# Skaarhoj_BI8-SE-C30.net
KiCad netlist of a schematic drawn in EAGLE
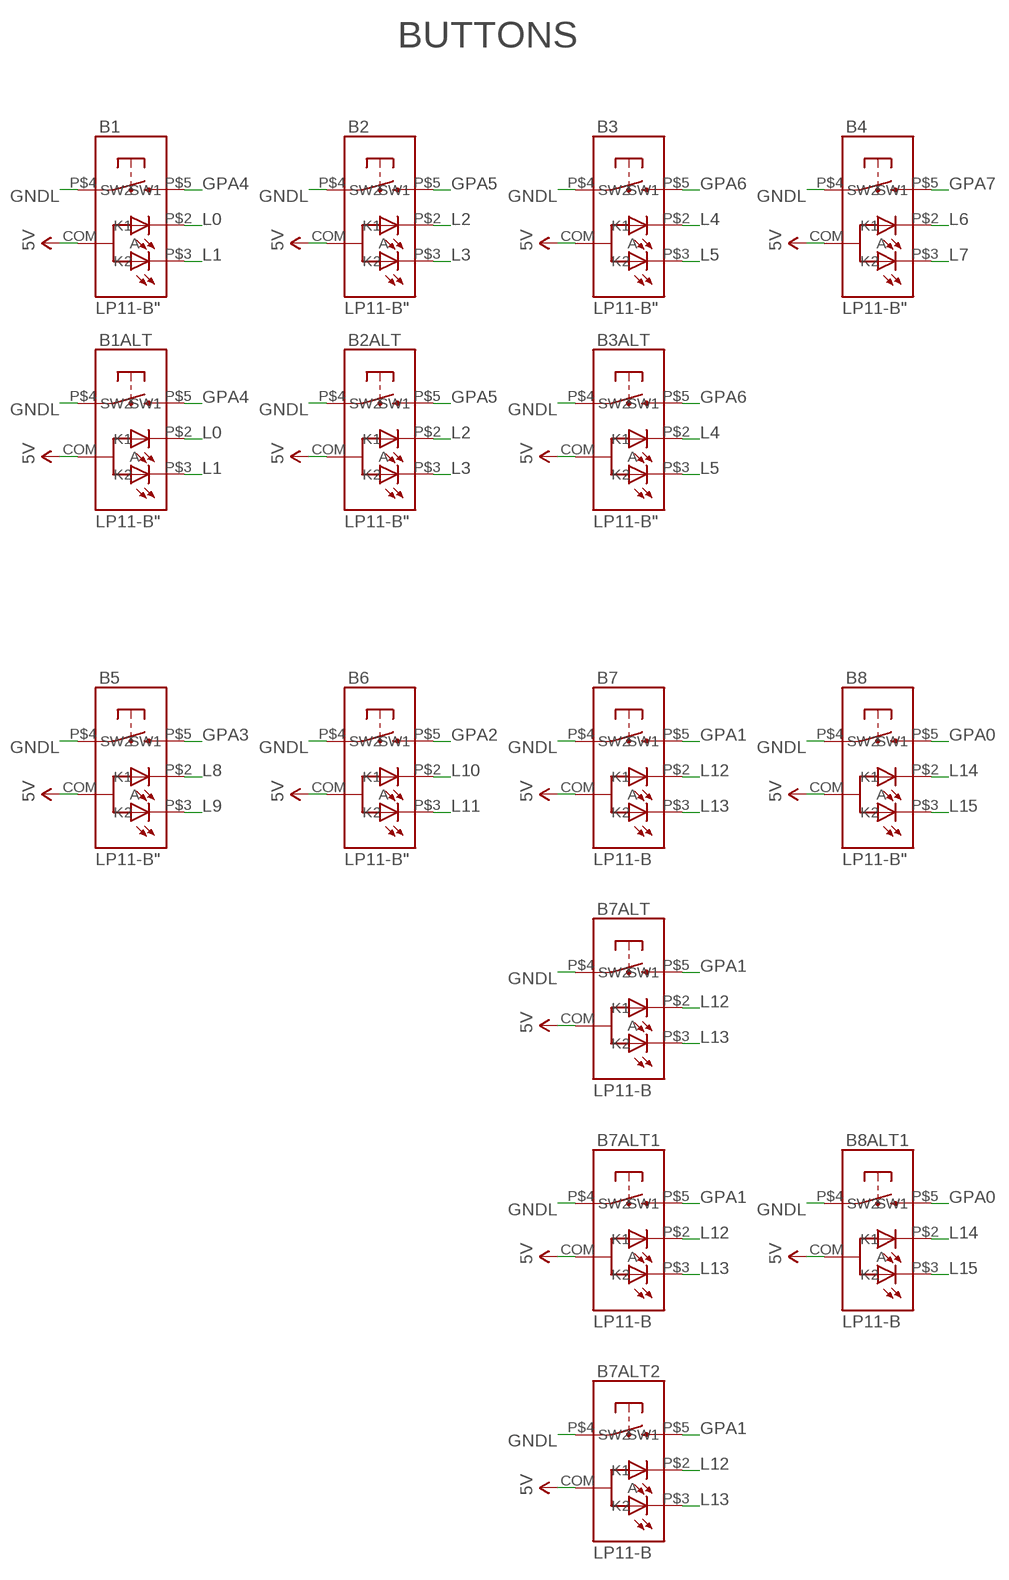
[diagram p0: schematic, sheet 1, part 1 of 2]
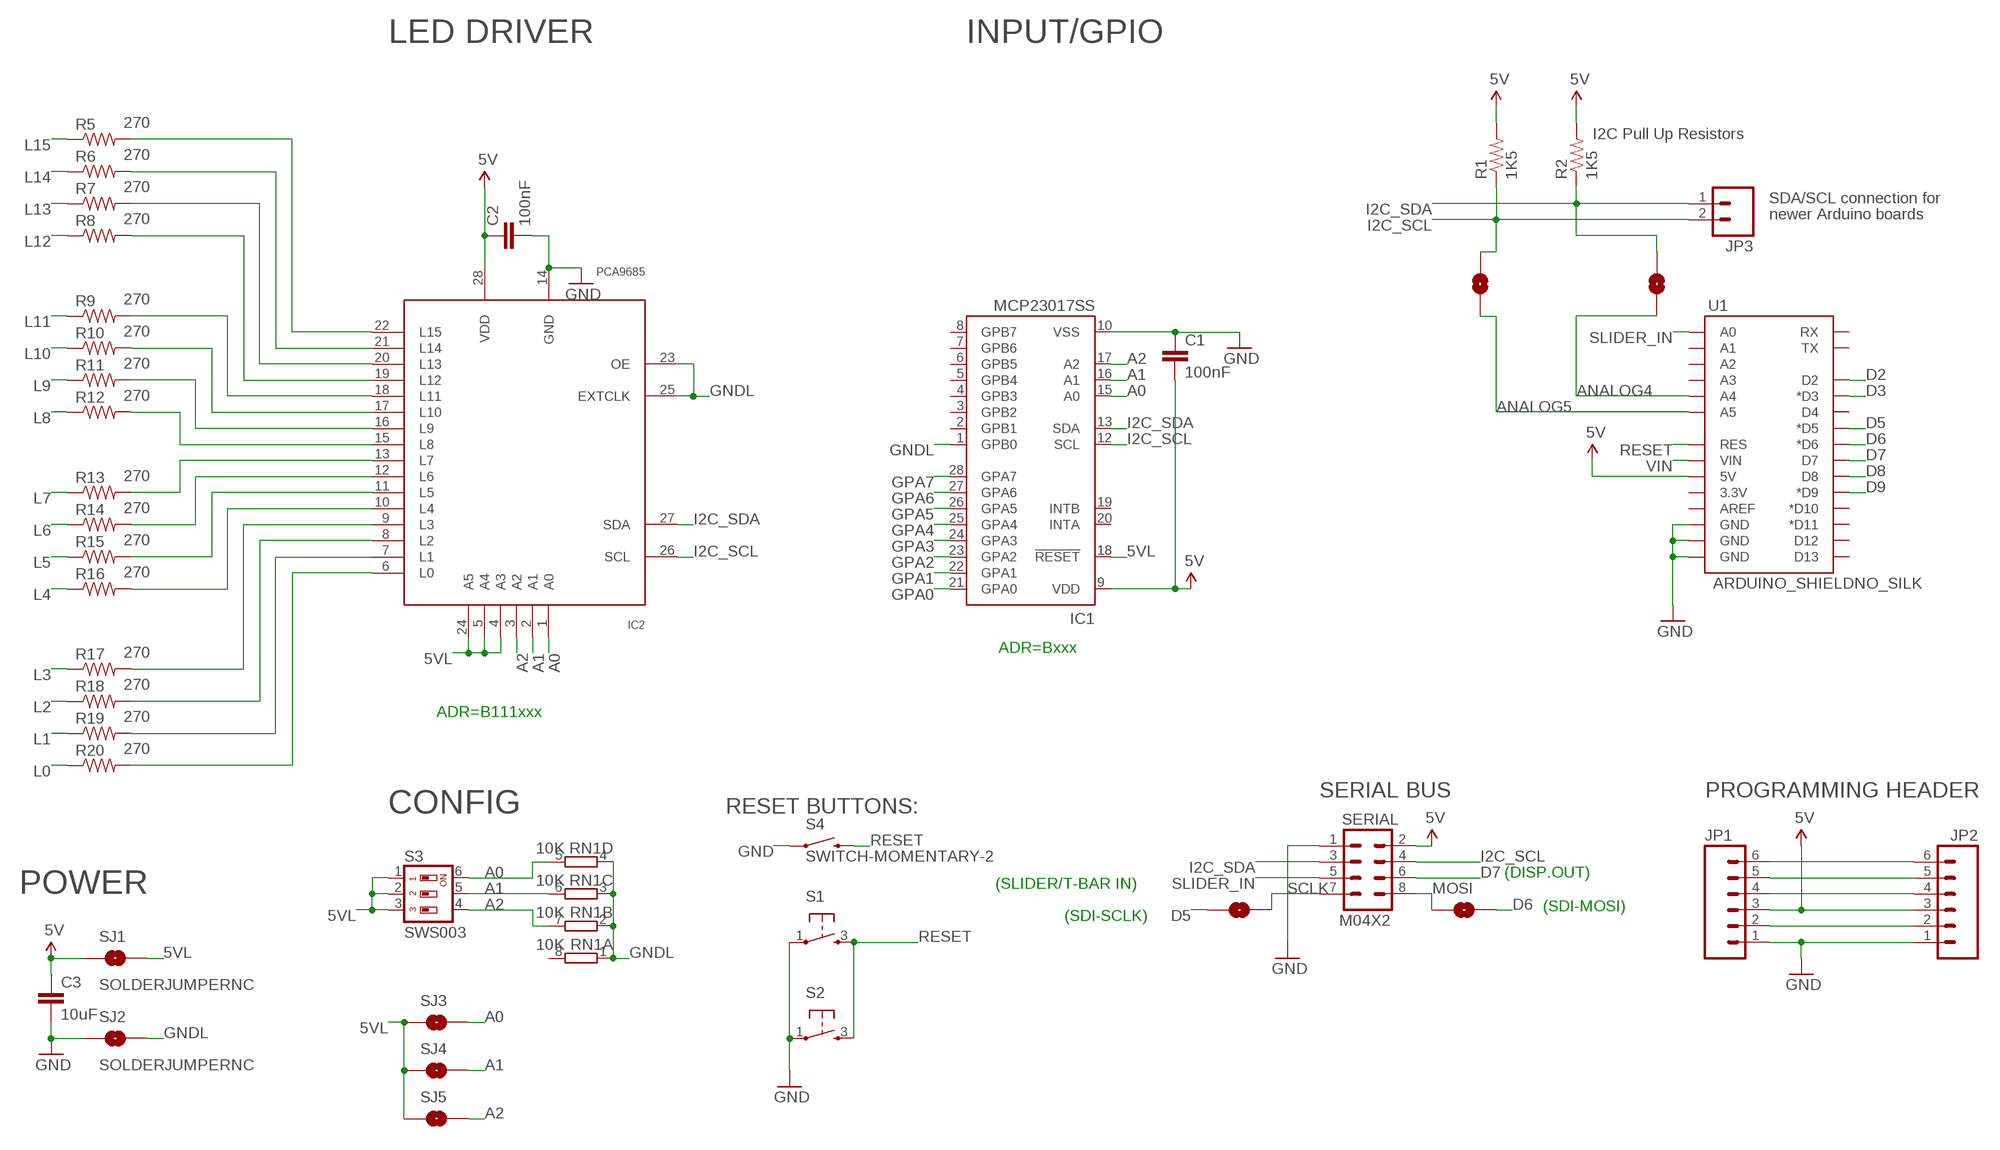
[diagram p1: schematic, sheet 1, part 2 of 2]

(export (version "E")
  (design (tool "Eeschema 10.0.6"))
  (components
    (comp (ref "B1")
      (value "LP11-B\"")
      (footprint "eagle-import:LP11")
      (libsource (lib "eagle-import") (part "LP11-B{dblquote}"))
    )
    (comp (ref "B1ALT")
      (value "LP11-B\"")
      (footprint "eagle-import:LP11")
      (libsource (lib "eagle-import") (part "LP11-B{dblquote}"))
    )
    (comp (ref "B2")
      (value "LP11-B\"")
      (footprint "eagle-import:LP11")
      (libsource (lib "eagle-import") (part "LP11-B{dblquote}"))
    )
    (comp (ref "B2ALT")
      (value "LP11-B\"")
      (footprint "eagle-import:LP11")
      (libsource (lib "eagle-import") (part "LP11-B{dblquote}"))
    )
    (comp (ref "B3")
      (value "LP11-B\"")
      (footprint "eagle-import:LP11")
      (libsource (lib "eagle-import") (part "LP11-B{dblquote}"))
    )
    (comp (ref "B3ALT")
      (value "LP11-B\"")
      (footprint "eagle-import:LP11")
      (libsource (lib "eagle-import") (part "LP11-B{dblquote}"))
    )
    (comp (ref "B4")
      (value "LP11-B\"")
      (footprint "eagle-import:LP11")
      (libsource (lib "eagle-import") (part "LP11-B{dblquote}"))
    )
    (comp (ref "B5")
      (value "LP11-B\"")
      (footprint "eagle-import:LP11")
      (libsource (lib "eagle-import") (part "LP11-B{dblquote}"))
    )
    (comp (ref "B6")
      (value "LP11-B\"")
      (footprint "eagle-import:LP11")
      (libsource (lib "eagle-import") (part "LP11-B{dblquote}"))
    )
    (comp (ref "B7")
      (value "LP11-B")
      (footprint "eagle-import:LP11_NOFIXHOLES")
      (libsource (lib "eagle-import") (part "LP11-B"))
    )
    (comp (ref "B7ALT")
      (value "LP11-B")
      (footprint "eagle-import:LP11_NOFIXHOLES")
      (libsource (lib "eagle-import") (part "LP11-B"))
    )
    (comp (ref "B7ALT1")
      (value "LP11-B")
      (footprint "eagle-import:LP11_NOFIXHOLES")
      (libsource (lib "eagle-import") (part "LP11-B"))
    )
    (comp (ref "B7ALT2")
      (value "LP11-B")
      (footprint "eagle-import:LP11_NOFIXHOLES")
      (libsource (lib "eagle-import") (part "LP11-B"))
    )
    (comp (ref "B8")
      (value "LP11-B\"")
      (footprint "eagle-import:LP11")
      (libsource (lib "eagle-import") (part "LP11-B{dblquote}"))
    )
    (comp (ref "B8ALT1")
      (value "LP11-B")
      (footprint "eagle-import:LP11_NOFIXHOLES")
      (libsource (lib "eagle-import") (part "LP11-B"))
    )
    (comp (ref "C1")
      (value "100nF")
      (footprint "eagle-import:0603-CAP")
      (libsource (lib "eagle-import") (part "CAP0603-CAP"))
    )
    (comp (ref "C2")
      (value "100nF")
      (footprint "eagle-import:0603-CAP")
      (libsource (lib "eagle-import") (part "CAP0603-CAP"))
    )
    (comp (ref "C3")
      (value "10uF")
      (footprint "eagle-import:0805")
      (libsource (lib "eagle-import") (part "CAP0805"))
    )
    (comp (ref "IC1")
      (value "MCP23017SS")
      (footprint "eagle-import:SSOP28")
      (fields
        (field (name "MF") "MICROCHIP")
        (field (name "MPN") "MCP23017-E/SS")
        (field (name "MPN_1") "MCP23017-E/SS")
        (field (name "OC_FARNELL") "1467674")
        (field (name "OC_NEWARK") "31K2960")
      )
      (libsource (lib "eagle-import") (part "MCP23017SS"))
    )
    (comp (ref "IC2")
      (value "PCA9685")
      (footprint "eagle-import:TSSOP28")
      (libsource (lib "eagle-import") (part "PCA9685"))
    )
    (comp (ref "JP1")
      (value "M06POLAR")
      (footprint "eagle-import:MOLEX-1X6")
      (libsource (lib "eagle-import") (part "M06POLAR"))
    )
    (comp (ref "JP2")
      (value "M06POLAR")
      (footprint "eagle-import:MOLEX-1X6")
      (libsource (lib "eagle-import") (part "M06POLAR"))
    )
    (comp (ref "JP3")
      (value "M02PTH")
      (footprint "eagle-import:1X02")
      (libsource (lib "eagle-import") (part "M02PTH"))
    )
    (comp (ref "MOSI->D6")
      (value "SOLDERJUMPERNC")
      (footprint "eagle-import:SJ_2S")
      (libsource (lib "eagle-import") (part "SOLDERJUMPERNC"))
    )
    (comp (ref "R1")
      (value "1K5")
      (footprint "eagle-import:0603-RES")
      (libsource (lib "eagle-import") (part "RESISTOR0603-RES"))
    )
    (comp (ref "R2")
      (value "1K5")
      (footprint "eagle-import:0603-RES")
      (libsource (lib "eagle-import") (part "RESISTOR0603-RES"))
    )
    (comp (ref "R5")
      (value "270")
      (footprint "eagle-import:0603-RES")
      (libsource (lib "eagle-import") (part "RESISTOR0603-RES"))
    )
    (comp (ref "R6")
      (value "270")
      (footprint "eagle-import:0603-RES")
      (libsource (lib "eagle-import") (part "RESISTOR0603-RES"))
    )
    (comp (ref "R7")
      (value "270")
      (footprint "eagle-import:0603-RES")
      (libsource (lib "eagle-import") (part "RESISTOR0603-RES"))
    )
    (comp (ref "R8")
      (value "270")
      (footprint "eagle-import:0603-RES")
      (libsource (lib "eagle-import") (part "RESISTOR0603-RES"))
    )
    (comp (ref "R9")
      (value "270")
      (footprint "eagle-import:0603-RES")
      (libsource (lib "eagle-import") (part "RESISTOR0603-RES"))
    )
    (comp (ref "R10")
      (value "270")
      (footprint "eagle-import:0603-RES")
      (libsource (lib "eagle-import") (part "RESISTOR0603-RES"))
    )
    (comp (ref "R11")
      (value "270")
      (footprint "eagle-import:0603-RES")
      (libsource (lib "eagle-import") (part "RESISTOR0603-RES"))
    )
    (comp (ref "R12")
      (value "270")
      (footprint "eagle-import:0603-RES")
      (libsource (lib "eagle-import") (part "RESISTOR0603-RES"))
    )
    (comp (ref "R13")
      (value "270")
      (footprint "eagle-import:0603-RES")
      (libsource (lib "eagle-import") (part "RESISTOR0603-RES"))
    )
    (comp (ref "R14")
      (value "270")
      (footprint "eagle-import:0603-RES")
      (libsource (lib "eagle-import") (part "RESISTOR0603-RES"))
    )
    (comp (ref "R15")
      (value "270")
      (footprint "eagle-import:0603-RES")
      (libsource (lib "eagle-import") (part "RESISTOR0603-RES"))
    )
    (comp (ref "R16")
      (value "270")
      (footprint "eagle-import:0603-RES")
      (libsource (lib "eagle-import") (part "RESISTOR0603-RES"))
    )
    (comp (ref "R17")
      (value "270")
      (footprint "eagle-import:0603-RES")
      (libsource (lib "eagle-import") (part "RESISTOR0603-RES"))
    )
    (comp (ref "R18")
      (value "270")
      (footprint "eagle-import:0603-RES")
      (libsource (lib "eagle-import") (part "RESISTOR0603-RES"))
    )
    (comp (ref "R19")
      (value "270")
      (footprint "eagle-import:0603-RES")
      (libsource (lib "eagle-import") (part "RESISTOR0603-RES"))
    )
    (comp (ref "R20")
      (value "270")
      (footprint "eagle-import:0603-RES")
      (libsource (lib "eagle-import") (part "RESISTOR0603-RES"))
    )
    (comp (ref "RN1")
      (value "10K")
      (footprint "eagle-import:CAY16_HAND")
      (libsource (lib "eagle-import") (part "4R-NCAY16"))
    )
    (comp (ref "S1")
      (value "TAC_SWITCH")
      (footprint "eagle-import:PUSHBUTTON")
      (libsource (lib "eagle-import") (part "TAC_SWITCH"))
    )
    (comp (ref "S2")
      (value "TAC_SWITCH")
      (footprint "eagle-import:PUSHBUTTON")
      (libsource (lib "eagle-import") (part "TAC_SWITCH"))
    )
    (comp (ref "S3")
      (value "SWS003")
      (footprint "eagle-import:SMS-003")
      (libsource (lib "eagle-import") (part "SWS003"))
    )
    (comp (ref "S3->A2")
      (value "SOLDERJUMPERNC")
      (footprint "eagle-import:SJ_2S")
      (libsource (lib "eagle-import") (part "SOLDERJUMPERNC"))
    )
    (comp (ref "S3->A3")
      (value "SOLDERJUMPERNC")
      (footprint "eagle-import:SJ_2S")
      (libsource (lib "eagle-import") (part "SOLDERJUMPERNC"))
    )
    (comp (ref "S4")
      (value "SWITCH-MOMENTARY-2")
      (footprint "eagle-import:TACTILE_SWITCH_TALL")
      (libsource (lib "eagle-import") (part "SWITCH-MOMENTARY-2"))
    )
    (comp (ref "SCLK->D5")
      (value "SOLDERJUMPERNC")
      (footprint "eagle-import:SJ_2S")
      (libsource (lib "eagle-import") (part "SOLDERJUMPERNC"))
    )
    (comp (ref "SERIAL")
      (value "M04X2")
      (footprint "eagle-import:2X4")
      (libsource (lib "eagle-import") (part "M04X2"))
    )
    (comp (ref "SJ1")
      (value "SOLDERJUMPERNC")
      (footprint "eagle-import:SJ_2S")
      (libsource (lib "eagle-import") (part "SOLDERJUMPERNC"))
    )
    (comp (ref "SJ2")
      (value "SOLDERJUMPERNC")
      (footprint "eagle-import:SJ_2S")
      (libsource (lib "eagle-import") (part "SOLDERJUMPERNC"))
    )
    (comp (ref "SJ3")
      (value "SOLDERJUMPERNC")
      (footprint "eagle-import:SJ_2S")
      (libsource (lib "eagle-import") (part "SOLDERJUMPERNC"))
    )
    (comp (ref "SJ4")
      (value "SOLDERJUMPERNC")
      (footprint "eagle-import:SJ_2S")
      (libsource (lib "eagle-import") (part "SOLDERJUMPERNC"))
    )
    (comp (ref "SJ5")
      (value "SOLDERJUMPERNC")
      (footprint "eagle-import:SJ_2S")
      (libsource (lib "eagle-import") (part "SOLDERJUMPERNC"))
    )
    (comp (ref "U1")
      (value "ARDUINO_SHIELDNO_SILK")
      (footprint "eagle-import:DUEMILANOVE_VIAS")
      (libsource (lib "eagle-import") (part "ARDUINO_SHIELDNO_SILK"))
    )
  )
  (nets
    (net (code "1") (name "/5VL") (class "Default")
      (node (ref "IC1") (pin "18") (pinfunction "~{RESET}_18") (pintype "input"))
      (node (ref "IC2") (pin "24") (pinfunction "A5_24") (pintype "input"))
      (node (ref "IC2") (pin "4") (pinfunction "A3_4") (pintype "input"))
      (node (ref "IC2") (pin "5") (pinfunction "A4_5") (pintype "input"))
      (node (ref "S3") (pin "1") (pinfunction "1_1") (pintype "passive"))
      (node (ref "S3") (pin "2") (pinfunction "2_2") (pintype "passive"))
      (node (ref "S3") (pin "3") (pinfunction "3_3") (pintype "passive"))
      (node (ref "SJ1") (pin "2") (pinfunction "2_2") (pintype "passive"))
      (node (ref "SJ3") (pin "1") (pinfunction "1_1") (pintype "passive"))
      (node (ref "SJ4") (pin "1") (pinfunction "1_1") (pintype "passive"))
      (node (ref "SJ5") (pin "1") (pinfunction "1_1") (pintype "passive"))
    )
    (net (code "2") (name "/A0") (class "Default")
      (node (ref "IC1") (pin "15") (pinfunction "A0_15") (pintype "input"))
      (node (ref "IC2") (pin "1") (pinfunction "A0_1") (pintype "input"))
      (node (ref "RN1") (pin "5") (pinfunction "2_5") (pintype "passive"))
      (node (ref "S3") (pin "6") (pinfunction "6_6") (pintype "passive"))
      (node (ref "SJ3") (pin "2") (pinfunction "2_2") (pintype "passive"))
    )
    (net (code "3") (name "/A1") (class "Default")
      (node (ref "IC1") (pin "16") (pinfunction "A1_16") (pintype "input"))
      (node (ref "IC2") (pin "2") (pinfunction "A1_2") (pintype "input"))
      (node (ref "RN1") (pin "6") (pinfunction "2_6") (pintype "passive"))
      (node (ref "S3") (pin "5") (pinfunction "5_5") (pintype "passive"))
      (node (ref "SJ4") (pin "2") (pinfunction "2_2") (pintype "passive"))
    )
    (net (code "4") (name "/A2") (class "Default")
      (node (ref "IC1") (pin "17") (pinfunction "A2_17") (pintype "input"))
      (node (ref "IC2") (pin "3") (pinfunction "A2_3") (pintype "input"))
      (node (ref "RN1") (pin "7") (pinfunction "2_7") (pintype "passive"))
      (node (ref "S3") (pin "4") (pinfunction "4_4") (pintype "passive"))
      (node (ref "SJ5") (pin "2") (pinfunction "2_2") (pintype "passive"))
    )
    (net (code "5") (name "/ANALOG4") (class "Default")
      (node (ref "S3->A3") (pin "2") (pinfunction "2_2") (pintype "passive"))
      (node (ref "U1") (pin "A4") (pinfunction "A4_A4") (pintype "bidirectional"))
    )
    (net (code "6") (name "/ANALOG5") (class "Default")
      (node (ref "S3->A2") (pin "2") (pinfunction "2_2") (pintype "passive"))
      (node (ref "U1") (pin "A5") (pinfunction "A5_A5") (pintype "bidirectional"))
    )
    (net (code "7") (name "/D2") (class "Default")
      (node (ref "U1") (pin "D2") (pinfunction "D2_D2") (pintype "bidirectional"))
    )
    (net (code "8") (name "/D3") (class "Default")
      (node (ref "U1") (pin "D3") (pinfunction "*D3_D3") (pintype "bidirectional"))
    )
    (net (code "9") (name "/D5") (class "Default")
      (node (ref "SCLK->D5") (pin "1") (pinfunction "1_1") (pintype "passive"))
      (node (ref "U1") (pin "D5") (pinfunction "*D5_D5") (pintype "bidirectional"))
    )
    (net (code "10") (name "/D6") (class "Default")
      (node (ref "MOSI->D6") (pin "2") (pinfunction "2_2") (pintype "passive"))
      (node (ref "U1") (pin "D6") (pinfunction "*D6_D6") (pintype "bidirectional"))
    )
    (net (code "11") (name "/D7") (class "Default")
      (node (ref "SERIAL") (pin "6") (pinfunction "6_6") (pintype "passive"))
      (node (ref "U1") (pin "D7") (pinfunction "D7_D7") (pintype "bidirectional"))
    )
    (net (code "12") (name "/D8") (class "Default")
      (node (ref "U1") (pin "D8") (pinfunction "D8_D8") (pintype "bidirectional"))
    )
    (net (code "13") (name "/D9") (class "Default")
      (node (ref "U1") (pin "D9") (pinfunction "*D9_D9") (pintype "bidirectional"))
    )
    (net (code "14") (name "/GNDL") (class "Default")
      (node (ref "B1") (pin "P$4") (pinfunction "SW1_P$4") (pintype "bidirectional"))
      (node (ref "B1ALT") (pin "P$4") (pinfunction "SW1_P$4") (pintype "bidirectional"))
      (node (ref "B2") (pin "P$4") (pinfunction "SW1_P$4") (pintype "bidirectional"))
      (node (ref "B2ALT") (pin "P$4") (pinfunction "SW1_P$4") (pintype "bidirectional"))
      (node (ref "B3") (pin "P$4") (pinfunction "SW1_P$4") (pintype "bidirectional"))
      (node (ref "B3ALT") (pin "P$4") (pinfunction "SW1_P$4") (pintype "bidirectional"))
      (node (ref "B4") (pin "P$4") (pinfunction "SW1_P$4") (pintype "bidirectional"))
      (node (ref "B5") (pin "P$4") (pinfunction "SW1_P$4") (pintype "bidirectional"))
      (node (ref "B6") (pin "P$4") (pinfunction "SW1_P$4") (pintype "bidirectional"))
      (node (ref "B7") (pin "P$4") (pinfunction "SW1_P$4") (pintype "bidirectional"))
      (node (ref "B7ALT") (pin "P$4") (pinfunction "SW1_P$4") (pintype "bidirectional"))
      (node (ref "B7ALT1") (pin "P$4") (pinfunction "SW1_P$4") (pintype "bidirectional"))
      (node (ref "B7ALT2") (pin "P$4") (pinfunction "SW1_P$4") (pintype "bidirectional"))
      (node (ref "B8") (pin "P$4") (pinfunction "SW1_P$4") (pintype "bidirectional"))
      (node (ref "B8ALT1") (pin "P$4") (pinfunction "SW1_P$4") (pintype "bidirectional"))
      (node (ref "IC1") (pin "1") (pinfunction "GPB0_1") (pintype "bidirectional"))
      (node (ref "IC2") (pin "23") (pinfunction "OE_23") (pintype "input"))
      (node (ref "IC2") (pin "25") (pinfunction "EXTCLK_25") (pintype "input"))
      (node (ref "RN1") (pin "1") (pinfunction "1_1") (pintype "passive"))
      (node (ref "RN1") (pin "2") (pinfunction "1_2") (pintype "passive"))
      (node (ref "RN1") (pin "3") (pinfunction "1_3") (pintype "passive"))
      (node (ref "RN1") (pin "4") (pinfunction "1_4") (pintype "passive"))
      (node (ref "SJ2") (pin "2") (pinfunction "2_2") (pintype "passive"))
    )
    (net (code "15") (name "/GPA0") (class "Default")
      (node (ref "B8") (pin "P$5") (pinfunction "SW2_P$5") (pintype "bidirectional"))
      (node (ref "B8ALT1") (pin "P$5") (pinfunction "SW2_P$5") (pintype "bidirectional"))
      (node (ref "IC1") (pin "21") (pinfunction "GPA0_21") (pintype "bidirectional"))
    )
    (net (code "16") (name "/GPA1") (class "Default")
      (node (ref "B7") (pin "P$5") (pinfunction "SW2_P$5") (pintype "bidirectional"))
      (node (ref "B7ALT") (pin "P$5") (pinfunction "SW2_P$5") (pintype "bidirectional"))
      (node (ref "B7ALT1") (pin "P$5") (pinfunction "SW2_P$5") (pintype "bidirectional"))
      (node (ref "B7ALT2") (pin "P$5") (pinfunction "SW2_P$5") (pintype "bidirectional"))
      (node (ref "IC1") (pin "22") (pinfunction "GPA1_22") (pintype "bidirectional"))
    )
    (net (code "17") (name "/GPA2") (class "Default")
      (node (ref "B6") (pin "P$5") (pinfunction "SW2_P$5") (pintype "bidirectional"))
      (node (ref "IC1") (pin "23") (pinfunction "GPA2_23") (pintype "bidirectional"))
    )
    (net (code "18") (name "/GPA3") (class "Default")
      (node (ref "B5") (pin "P$5") (pinfunction "SW2_P$5") (pintype "bidirectional"))
      (node (ref "IC1") (pin "24") (pinfunction "GPA3_24") (pintype "bidirectional"))
    )
    (net (code "19") (name "/GPA4") (class "Default")
      (node (ref "B1") (pin "P$5") (pinfunction "SW2_P$5") (pintype "bidirectional"))
      (node (ref "B1ALT") (pin "P$5") (pinfunction "SW2_P$5") (pintype "bidirectional"))
      (node (ref "IC1") (pin "25") (pinfunction "GPA4_25") (pintype "bidirectional"))
    )
    (net (code "20") (name "/GPA5") (class "Default")
      (node (ref "B2") (pin "P$5") (pinfunction "SW2_P$5") (pintype "bidirectional"))
      (node (ref "B2ALT") (pin "P$5") (pinfunction "SW2_P$5") (pintype "bidirectional"))
      (node (ref "IC1") (pin "26") (pinfunction "GPA5_26") (pintype "bidirectional"))
    )
    (net (code "21") (name "/GPA6") (class "Default")
      (node (ref "B3") (pin "P$5") (pinfunction "SW2_P$5") (pintype "bidirectional"))
      (node (ref "B3ALT") (pin "P$5") (pinfunction "SW2_P$5") (pintype "bidirectional"))
      (node (ref "IC1") (pin "27") (pinfunction "GPA6_27") (pintype "bidirectional"))
    )
    (net (code "22") (name "/GPA7") (class "Default")
      (node (ref "B4") (pin "P$5") (pinfunction "SW2_P$5") (pintype "bidirectional"))
      (node (ref "IC1") (pin "28") (pinfunction "GPA7_28") (pintype "bidirectional"))
    )
    (net (code "23") (name "/I2C_SCL") (class "Default")
      (node (ref "IC1") (pin "12") (pinfunction "SCL_12") (pintype "input"))
      (node (ref "IC2") (pin "26") (pinfunction "SCL_26") (pintype "input"))
      (node (ref "JP3") (pin "2") (pinfunction "2_2") (pintype "passive"))
      (node (ref "R1") (pin "1") (pinfunction "1_1") (pintype "passive"))
      (node (ref "S3->A2") (pin "1") (pinfunction "1_1") (pintype "passive"))
      (node (ref "SERIAL") (pin "4") (pinfunction "4_4") (pintype "passive"))
    )
    (net (code "24") (name "/I2C_SDA") (class "Default")
      (node (ref "IC1") (pin "13") (pinfunction "SDA_13") (pintype "bidirectional"))
      (node (ref "IC2") (pin "27") (pinfunction "SDA_27") (pintype "input"))
      (node (ref "JP3") (pin "1") (pinfunction "1_1") (pintype "passive"))
      (node (ref "R2") (pin "1") (pinfunction "1_1") (pintype "passive"))
      (node (ref "S3->A3") (pin "1") (pinfunction "1_1") (pintype "passive"))
      (node (ref "SERIAL") (pin "3") (pinfunction "3_3") (pintype "passive"))
    )
    (net (code "25") (name "/L0") (class "Default")
      (node (ref "B1") (pin "P$2") (pinfunction "K1_P$2") (pintype "bidirectional"))
      (node (ref "B1ALT") (pin "P$2") (pinfunction "K1_P$2") (pintype "bidirectional"))
      (node (ref "R20") (pin "1") (pinfunction "1_1") (pintype "passive"))
    )
    (net (code "26") (name "/L1") (class "Default")
      (node (ref "B1") (pin "P$3") (pinfunction "K2_P$3") (pintype "bidirectional"))
      (node (ref "B1ALT") (pin "P$3") (pinfunction "K2_P$3") (pintype "bidirectional"))
      (node (ref "R19") (pin "1") (pinfunction "1_1") (pintype "passive"))
    )
    (net (code "27") (name "/L2") (class "Default")
      (node (ref "B2") (pin "P$2") (pinfunction "K1_P$2") (pintype "bidirectional"))
      (node (ref "B2ALT") (pin "P$2") (pinfunction "K1_P$2") (pintype "bidirectional"))
      (node (ref "R18") (pin "1") (pinfunction "1_1") (pintype "passive"))
    )
    (net (code "28") (name "/L3") (class "Default")
      (node (ref "B2") (pin "P$3") (pinfunction "K2_P$3") (pintype "bidirectional"))
      (node (ref "B2ALT") (pin "P$3") (pinfunction "K2_P$3") (pintype "bidirectional"))
      (node (ref "R17") (pin "1") (pinfunction "1_1") (pintype "passive"))
    )
    (net (code "29") (name "/L4") (class "Default")
      (node (ref "B3") (pin "P$2") (pinfunction "K1_P$2") (pintype "bidirectional"))
      (node (ref "B3ALT") (pin "P$2") (pinfunction "K1_P$2") (pintype "bidirectional"))
      (node (ref "R16") (pin "1") (pinfunction "1_1") (pintype "passive"))
    )
    (net (code "30") (name "/L5") (class "Default")
      (node (ref "B3") (pin "P$3") (pinfunction "K2_P$3") (pintype "bidirectional"))
      (node (ref "B3ALT") (pin "P$3") (pinfunction "K2_P$3") (pintype "bidirectional"))
      (node (ref "R15") (pin "1") (pinfunction "1_1") (pintype "passive"))
    )
    (net (code "31") (name "/L6") (class "Default")
      (node (ref "B4") (pin "P$2") (pinfunction "K1_P$2") (pintype "bidirectional"))
      (node (ref "R14") (pin "1") (pinfunction "1_1") (pintype "passive"))
    )
    (net (code "32") (name "/L7") (class "Default")
      (node (ref "B4") (pin "P$3") (pinfunction "K2_P$3") (pintype "bidirectional"))
      (node (ref "R13") (pin "1") (pinfunction "1_1") (pintype "passive"))
    )
    (net (code "33") (name "/L8") (class "Default")
      (node (ref "B5") (pin "P$2") (pinfunction "K1_P$2") (pintype "bidirectional"))
      (node (ref "R12") (pin "1") (pinfunction "1_1") (pintype "passive"))
    )
    (net (code "34") (name "/L9") (class "Default")
      (node (ref "B5") (pin "P$3") (pinfunction "K2_P$3") (pintype "bidirectional"))
      (node (ref "R11") (pin "1") (pinfunction "1_1") (pintype "passive"))
    )
    (net (code "35") (name "/L10") (class "Default")
      (node (ref "B6") (pin "P$2") (pinfunction "K1_P$2") (pintype "bidirectional"))
      (node (ref "R10") (pin "1") (pinfunction "1_1") (pintype "passive"))
    )
    (net (code "36") (name "/L11") (class "Default")
      (node (ref "B6") (pin "P$3") (pinfunction "K2_P$3") (pintype "bidirectional"))
      (node (ref "R9") (pin "1") (pinfunction "1_1") (pintype "passive"))
    )
    (net (code "37") (name "/L12") (class "Default")
      (node (ref "B7") (pin "P$2") (pinfunction "K1_P$2") (pintype "bidirectional"))
      (node (ref "B7ALT") (pin "P$2") (pinfunction "K1_P$2") (pintype "bidirectional"))
      (node (ref "B7ALT1") (pin "P$2") (pinfunction "K1_P$2") (pintype "bidirectional"))
      (node (ref "B7ALT2") (pin "P$2") (pinfunction "K1_P$2") (pintype "bidirectional"))
      (node (ref "R8") (pin "1") (pinfunction "1_1") (pintype "passive"))
    )
    (net (code "38") (name "/L13") (class "Default")
      (node (ref "B7") (pin "P$3") (pinfunction "K2_P$3") (pintype "bidirectional"))
      (node (ref "B7ALT") (pin "P$3") (pinfunction "K2_P$3") (pintype "bidirectional"))
      (node (ref "B7ALT1") (pin "P$3") (pinfunction "K2_P$3") (pintype "bidirectional"))
      (node (ref "B7ALT2") (pin "P$3") (pinfunction "K2_P$3") (pintype "bidirectional"))
      (node (ref "R7") (pin "1") (pinfunction "1_1") (pintype "passive"))
    )
    (net (code "39") (name "/L14") (class "Default")
      (node (ref "B8") (pin "P$2") (pinfunction "K1_P$2") (pintype "bidirectional"))
      (node (ref "B8ALT1") (pin "P$2") (pinfunction "K1_P$2") (pintype "bidirectional"))
      (node (ref "R6") (pin "1") (pinfunction "1_1") (pintype "passive"))
    )
    (net (code "40") (name "/L15") (class "Default")
      (node (ref "B8") (pin "P$3") (pinfunction "K2_P$3") (pintype "bidirectional"))
      (node (ref "B8ALT1") (pin "P$3") (pinfunction "K2_P$3") (pintype "bidirectional"))
      (node (ref "R5") (pin "1") (pinfunction "1_1") (pintype "passive"))
    )
    (net (code "41") (name "/MOSI") (class "Default")
      (node (ref "MOSI->D6") (pin "1") (pinfunction "1_1") (pintype "passive"))
      (node (ref "SERIAL") (pin "8") (pinfunction "8_8") (pintype "passive"))
    )
    (net (code "42") (name "/RESET") (class "Default")
      (node (ref "S1") (pin "3") (pinfunction "3_3") (pintype "passive"))
      (node (ref "S2") (pin "3") (pinfunction "3_3") (pintype "passive"))
      (node (ref "S4") (pin "B2") (pinfunction "2_B2") (pintype "passive"))
      (node (ref "U1") (pin "RES") (pinfunction "RES_RES") (pintype "bidirectional"))
    )
    (net (code "43") (name "/SCLK") (class "Default")
      (node (ref "SCLK->D5") (pin "2") (pinfunction "2_2") (pintype "passive"))
      (node (ref "SERIAL") (pin "7") (pinfunction "7_7") (pintype "passive"))
    )
    (net (code "44") (name "/SLIDER_IN") (class "Default")
      (node (ref "SERIAL") (pin "5") (pinfunction "5_5") (pintype "passive"))
      (node (ref "U1") (pin "A0") (pinfunction "A0_A0") (pintype "bidirectional"))
    )
    (net (code "45") (name "/VIN") (class "Default")
      (node (ref "U1") (pin "VIN") (pinfunction "VIN_VIN") (pintype "bidirectional"))
    )
    (net (code "46") (name "5V") (class "Default")
      (node (ref "B1") (pin "COM") (pinfunction "A_COM") (pintype "bidirectional"))
      (node (ref "B1ALT") (pin "COM") (pinfunction "A_COM") (pintype "bidirectional"))
      (node (ref "B2") (pin "COM") (pinfunction "A_COM") (pintype "bidirectional"))
      (node (ref "B2ALT") (pin "COM") (pinfunction "A_COM") (pintype "bidirectional"))
      (node (ref "B3") (pin "COM") (pinfunction "A_COM") (pintype "bidirectional"))
      (node (ref "B3ALT") (pin "COM") (pinfunction "A_COM") (pintype "bidirectional"))
      (node (ref "B4") (pin "COM") (pinfunction "A_COM") (pintype "bidirectional"))
      (node (ref "B5") (pin "COM") (pinfunction "A_COM") (pintype "bidirectional"))
      (node (ref "B6") (pin "COM") (pinfunction "A_COM") (pintype "bidirectional"))
      (node (ref "B7") (pin "COM") (pinfunction "A_COM") (pintype "bidirectional"))
      (node (ref "B7ALT") (pin "COM") (pinfunction "A_COM") (pintype "bidirectional"))
      (node (ref "B7ALT1") (pin "COM") (pinfunction "A_COM") (pintype "bidirectional"))
      (node (ref "B7ALT2") (pin "COM") (pinfunction "A_COM") (pintype "bidirectional"))
      (node (ref "B8") (pin "COM") (pinfunction "A_COM") (pintype "bidirectional"))
      (node (ref "B8ALT1") (pin "COM") (pinfunction "A_COM") (pintype "bidirectional"))
      (node (ref "C1") (pin "2") (pinfunction "2_2") (pintype "passive"))
      (node (ref "C2") (pin "1") (pinfunction "1_1") (pintype "passive"))
      (node (ref "C3") (pin "1") (pinfunction "1_1") (pintype "passive"))
      (node (ref "IC1") (pin "9") (pinfunction "VDD_9") (pintype "power_in"))
      (node (ref "IC2") (pin "28") (pinfunction "VDD_28") (pintype "power_in"))
      (node (ref "JP1") (pin "3") (pinfunction "3_3") (pintype "passive"))
      (node (ref "JP2") (pin "3") (pinfunction "3_3") (pintype "passive"))
      (node (ref "R1") (pin "2") (pinfunction "2_2") (pintype "passive"))
      (node (ref "R2") (pin "2") (pinfunction "2_2") (pintype "passive"))
      (node (ref "SERIAL") (pin "2") (pinfunction "2_2") (pintype "passive"))
      (node (ref "SJ1") (pin "1") (pinfunction "1_1") (pintype "passive"))
      (node (ref "U1") (pin "5V") (pinfunction "5V_5V") (pintype "bidirectional"))
    )
    (net (code "47") (name "GND") (class "Default")
      (node (ref "C1") (pin "1") (pinfunction "1_1") (pintype "passive"))
      (node (ref "C2") (pin "2") (pinfunction "2_2") (pintype "passive"))
      (node (ref "C3") (pin "2") (pinfunction "2_2") (pintype "passive"))
      (node (ref "IC1") (pin "10") (pinfunction "VSS_10") (pintype "power_in"))
      (node (ref "IC2") (pin "14") (pinfunction "GND_14") (pintype "power_in"))
      (node (ref "JP1") (pin "1") (pinfunction "1_1") (pintype "passive"))
      (node (ref "JP2") (pin "1") (pinfunction "1_1") (pintype "passive"))
      (node (ref "S1") (pin "1") (pinfunction "1_1") (pintype "passive"))
      (node (ref "S2") (pin "1") (pinfunction "1_1") (pintype "passive"))
      (node (ref "S4") (pin "A2") (pinfunction "1_A2") (pintype "passive"))
      (node (ref "SERIAL") (pin "1") (pinfunction "1_1") (pintype "passive"))
      (node (ref "SJ2") (pin "1") (pinfunction "1_1") (pintype "passive"))
      (node (ref "U1") (pin "GND@0") (pinfunction "GND_GND@0") (pintype "bidirectional"))
      (node (ref "U1") (pin "GND@1") (pinfunction "GND_GND@1") (pintype "bidirectional"))
      (node (ref "U1") (pin "GND@2") (pinfunction "GND_GND@2") (pintype "bidirectional"))
    )
    (net (code "48") (name "Net-(IC2-L0)") (class "Default")
      (node (ref "IC2") (pin "6") (pinfunction "L0_6") (pintype "output"))
      (node (ref "R20") (pin "2") (pinfunction "2_2") (pintype "passive"))
    )
    (net (code "49") (name "Net-(IC2-L1)") (class "Default")
      (node (ref "IC2") (pin "7") (pinfunction "L1_7") (pintype "output"))
      (node (ref "R19") (pin "2") (pinfunction "2_2") (pintype "passive"))
    )
    (net (code "50") (name "Net-(IC2-L2)") (class "Default")
      (node (ref "IC2") (pin "8") (pinfunction "L2_8") (pintype "output"))
      (node (ref "R18") (pin "2") (pinfunction "2_2") (pintype "passive"))
    )
    (net (code "51") (name "Net-(IC2-L3)") (class "Default")
      (node (ref "IC2") (pin "9") (pinfunction "L3_9") (pintype "output"))
      (node (ref "R17") (pin "2") (pinfunction "2_2") (pintype "passive"))
    )
    (net (code "52") (name "Net-(IC2-L4)") (class "Default")
      (node (ref "IC2") (pin "10") (pinfunction "L4_10") (pintype "output"))
      (node (ref "R16") (pin "2") (pinfunction "2_2") (pintype "passive"))
    )
    (net (code "53") (name "Net-(IC2-L5)") (class "Default")
      (node (ref "IC2") (pin "11") (pinfunction "L5_11") (pintype "output"))
      (node (ref "R15") (pin "2") (pinfunction "2_2") (pintype "passive"))
    )
    (net (code "54") (name "Net-(IC2-L6)") (class "Default")
      (node (ref "IC2") (pin "12") (pinfunction "L6_12") (pintype "output"))
      (node (ref "R14") (pin "2") (pinfunction "2_2") (pintype "passive"))
    )
    (net (code "55") (name "Net-(IC2-L7)") (class "Default")
      (node (ref "IC2") (pin "13") (pinfunction "L7_13") (pintype "output"))
      (node (ref "R13") (pin "2") (pinfunction "2_2") (pintype "passive"))
    )
    (net (code "56") (name "Net-(IC2-L8)") (class "Default")
      (node (ref "IC2") (pin "15") (pinfunction "L8_15") (pintype "output"))
      (node (ref "R12") (pin "2") (pinfunction "2_2") (pintype "passive"))
    )
    (net (code "57") (name "Net-(IC2-L9)") (class "Default")
      (node (ref "IC2") (pin "16") (pinfunction "L9_16") (pintype "output"))
      (node (ref "R11") (pin "2") (pinfunction "2_2") (pintype "passive"))
    )
    (net (code "58") (name "Net-(IC2-L10)") (class "Default")
      (node (ref "IC2") (pin "17") (pinfunction "L10_17") (pintype "output"))
      (node (ref "R10") (pin "2") (pinfunction "2_2") (pintype "passive"))
    )
    (net (code "59") (name "Net-(IC2-L11)") (class "Default")
      (node (ref "IC2") (pin "18") (pinfunction "L11_18") (pintype "output"))
      (node (ref "R9") (pin "2") (pinfunction "2_2") (pintype "passive"))
    )
    (net (code "60") (name "Net-(IC2-L12)") (class "Default")
      (node (ref "IC2") (pin "19") (pinfunction "L12_19") (pintype "output"))
      (node (ref "R8") (pin "2") (pinfunction "2_2") (pintype "passive"))
    )
    (net (code "61") (name "Net-(IC2-L13)") (class "Default")
      (node (ref "IC2") (pin "20") (pinfunction "L13_20") (pintype "output"))
      (node (ref "R7") (pin "2") (pinfunction "2_2") (pintype "passive"))
    )
    (net (code "62") (name "Net-(IC2-L14)") (class "Default")
      (node (ref "IC2") (pin "21") (pinfunction "L14_21") (pintype "output"))
      (node (ref "R6") (pin "2") (pinfunction "2_2") (pintype "passive"))
    )
    (net (code "63") (name "Net-(IC2-L15)") (class "Default")
      (node (ref "IC2") (pin "22") (pinfunction "L15_22") (pintype "output"))
      (node (ref "R5") (pin "2") (pinfunction "2_2") (pintype "passive"))
    )
    (net (code "64") (name "Net-(JP1-Pad2)") (class "Default")
      (node (ref "JP1") (pin "2") (pinfunction "2_2") (pintype "passive"))
      (node (ref "JP2") (pin "2") (pinfunction "2_2") (pintype "passive"))
    )
    (net (code "65") (name "Net-(JP1-Pad4)") (class "Default")
      (node (ref "JP1") (pin "4") (pinfunction "4_4") (pintype "passive"))
      (node (ref "JP2") (pin "4") (pinfunction "4_4") (pintype "passive"))
    )
    (net (code "66") (name "Net-(JP1-Pad5)") (class "Default")
      (node (ref "JP1") (pin "5") (pinfunction "5_5") (pintype "passive"))
      (node (ref "JP2") (pin "5") (pinfunction "5_5") (pintype "passive"))
    )
    (net (code "67") (name "Net-(JP1-Pad6)") (class "Default")
      (node (ref "JP1") (pin "6") (pinfunction "6_6") (pintype "passive"))
      (node (ref "JP2") (pin "6") (pinfunction "6_6") (pintype "passive"))
    )
    (net (code "68") (name "unconnected-(IC1-GPB1-Pad2)") (class "Default")
      (node (ref "IC1") (pin "2") (pinfunction "GPB1_2") (pintype "bidirectional"))
    )
    (net (code "69") (name "unconnected-(IC1-GPB2-Pad3)") (class "Default")
      (node (ref "IC1") (pin "3") (pinfunction "GPB2_3") (pintype "bidirectional"))
    )
    (net (code "70") (name "unconnected-(IC1-GPB3-Pad4)") (class "Default")
      (node (ref "IC1") (pin "4") (pinfunction "GPB3_4") (pintype "bidirectional"))
    )
    (net (code "71") (name "unconnected-(IC1-GPB4-Pad5)") (class "Default")
      (node (ref "IC1") (pin "5") (pinfunction "GPB4_5") (pintype "bidirectional"))
    )
    (net (code "72") (name "unconnected-(IC1-GPB5-Pad6)") (class "Default")
      (node (ref "IC1") (pin "6") (pinfunction "GPB5_6") (pintype "bidirectional"))
    )
    (net (code "73") (name "unconnected-(IC1-GPB6-Pad7)") (class "Default")
      (node (ref "IC1") (pin "7") (pinfunction "GPB6_7") (pintype "bidirectional"))
    )
    (net (code "74") (name "unconnected-(IC1-GPB7-Pad8)") (class "Default")
      (node (ref "IC1") (pin "8") (pinfunction "GPB7_8") (pintype "bidirectional"))
    )
    (net (code "75") (name "unconnected-(IC1-INTA-Pad20)") (class "Default")
      (node (ref "IC1") (pin "20") (pinfunction "INTA_20") (pintype "output"))
    )
    (net (code "76") (name "unconnected-(IC1-INTB-Pad19)") (class "Default")
      (node (ref "IC1") (pin "19") (pinfunction "INTB_19") (pintype "output"))
    )
    (net (code "77") (name "unconnected-(RN1A-2-Pad8)") (class "Default")
      (node (ref "RN1") (pin "8") (pinfunction "2_8") (pintype "passive"))
    )
    (net (code "78") (name "unconnected-(U1-*D10-PadD10)") (class "Default")
      (node (ref "U1") (pin "D10") (pinfunction "*D10_D10") (pintype "bidirectional"))
    )
    (net (code "79") (name "unconnected-(U1-*D11-PadD11)") (class "Default")
      (node (ref "U1") (pin "D11") (pinfunction "*D11_D11") (pintype "bidirectional"))
    )
    (net (code "80") (name "unconnected-(U1-Pad3.3V)") (class "Default")
      (node (ref "U1") (pin "3.3V") (pinfunction "3.3V_3.3V") (pintype "bidirectional"))
    )
    (net (code "81") (name "unconnected-(U1-PadA1)") (class "Default")
      (node (ref "U1") (pin "A1") (pinfunction "A1_A1") (pintype "bidirectional"))
    )
    (net (code "82") (name "unconnected-(U1-PadA2)") (class "Default")
      (node (ref "U1") (pin "A2") (pinfunction "A2_A2") (pintype "bidirectional"))
    )
    (net (code "83") (name "unconnected-(U1-PadA3)") (class "Default")
      (node (ref "U1") (pin "A3") (pinfunction "A3_A3") (pintype "bidirectional"))
    )
    (net (code "84") (name "unconnected-(U1-PadAREF)") (class "Default")
      (node (ref "U1") (pin "AREF") (pinfunction "AREF_AREF") (pintype "bidirectional"))
    )
    (net (code "85") (name "unconnected-(U1-PadD4)") (class "Default")
      (node (ref "U1") (pin "D4") (pinfunction "D4_D4") (pintype "bidirectional"))
    )
    (net (code "86") (name "unconnected-(U1-PadD12)") (class "Default")
      (node (ref "U1") (pin "D12") (pinfunction "D12_D12") (pintype "bidirectional"))
    )
    (net (code "87") (name "unconnected-(U1-PadD13)") (class "Default")
      (node (ref "U1") (pin "D13") (pinfunction "D13_D13") (pintype "bidirectional"))
    )
    (net (code "88") (name "unconnected-(U1-PadRX)") (class "Default")
      (node (ref "U1") (pin "RX") (pinfunction "RX_RX") (pintype "bidirectional"))
    )
    (net (code "89") (name "unconnected-(U1-PadTX)") (class "Default")
      (node (ref "U1") (pin "TX") (pinfunction "TX_TX") (pintype "bidirectional"))
    )
  )
)
